# pwr.net
KiCad netlist of a schematic drawn in EAGLE
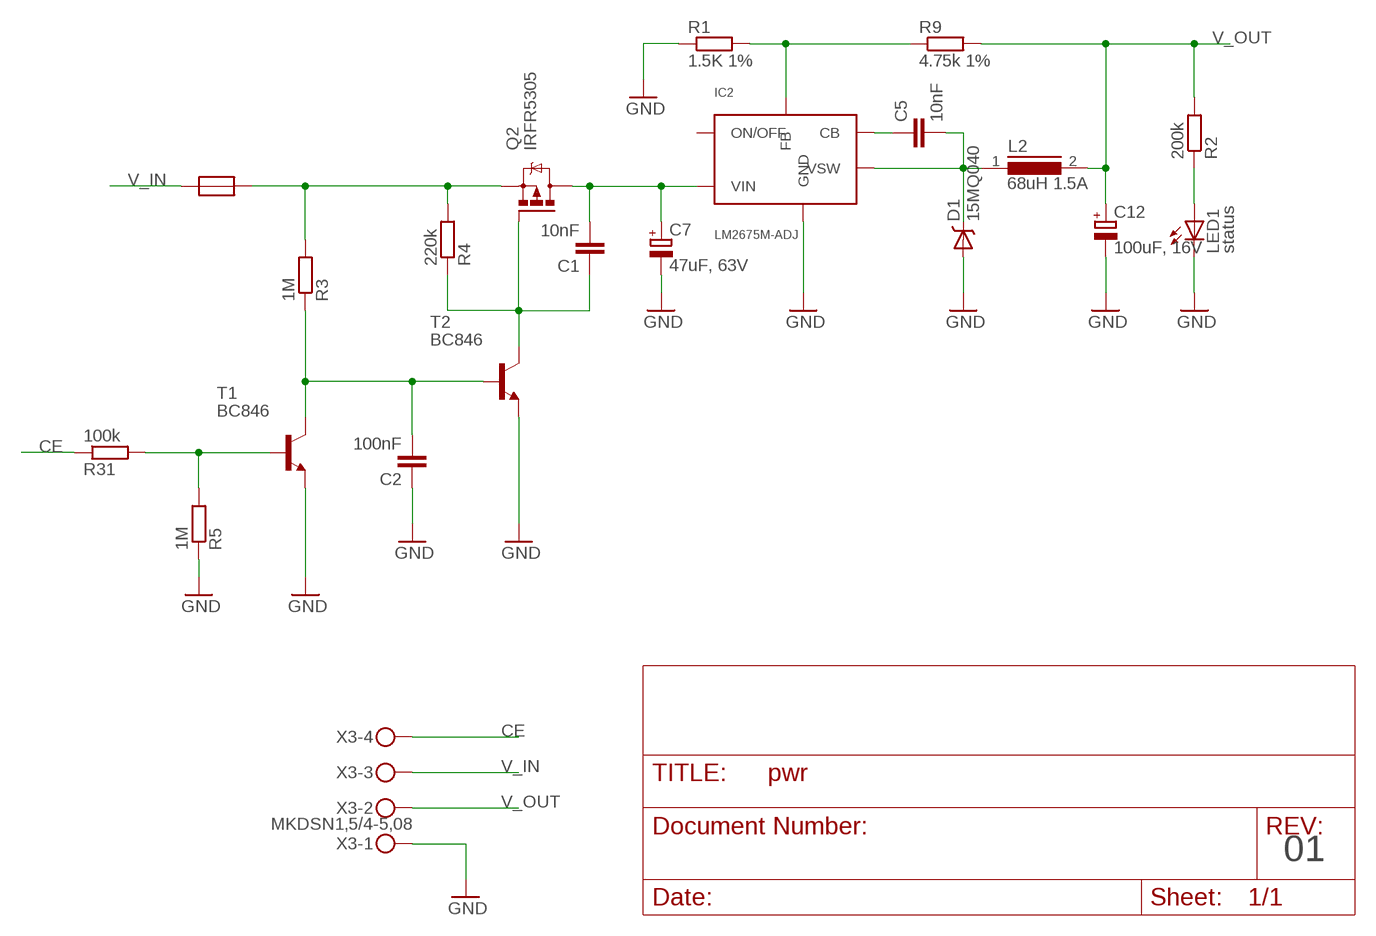
[diagram p0: schematic, sheet 1]

(export (version "E")
  (design (tool "Eeschema 10.0.6"))
  (components
    (comp (ref "C1")
      (value "10nF")
      (footprint "eagle-import:C0805")
      (libsource (lib "eagle-import") (part "C-EUC0805"))
    )
    (comp (ref "C2")
      (value "100nF")
      (footprint "eagle-import:C0805")
      (libsource (lib "eagle-import") (part "C-EUC0805"))
    )
    (comp (ref "C5")
      (value "10nF")
      (footprint "eagle-import:C0805")
      (libsource (lib "eagle-import") (part "C-EUC0805"))
    )
    (comp (ref "C7")
      (value "47uF, 63V")
      (footprint "eagle-import:PANASONIC_F")
      (libsource (lib "eagle-import") (part "CPOL-EUF"))
    )
    (comp (ref "C12")
      (value "100uF, 16V")
      (footprint "eagle-import:PANASONIC_D")
      (libsource (lib "eagle-import") (part "CPOL-EUD"))
    )
    (comp (ref "D1")
      (value "15MQ040")
      (footprint "eagle-import:SMA-DIODE")
      (libsource (lib "eagle-import") (part "DIODE-SCHOTTKY-MBRA140"))
    )
    (comp (ref "IC2")
      (value "LM2675M-ADJ")
      (footprint "eagle-import:SO-08")
      (libsource (lib "eagle-import") (part "LM2674"))
    )
    (comp (ref "L2")
      (value "68uH 1.5A")
      (footprint "eagle-import:DR125")
      (libsource (lib "eagle-import") (part "DR125"))
    )
    (comp (ref "LED1")
      (value "status")
      (footprint "eagle-import:CHIP-LED0805")
      (libsource (lib "eagle-import") (part "LEDCHIP-LED0805"))
    )
    (comp (ref "Q2")
      (value "IRFR5305")
      (footprint "eagle-import:D-PAK_TO252AA")
      (libsource (lib "eagle-import") (part "IRF?5305R"))
    )
    (comp (ref "R1")
      (value "1.5K 1%")
      (footprint "eagle-import:R0805W")
      (libsource (lib "eagle-import") (part "R-EU_R0805W"))
    )
    (comp (ref "R2")
      (value "200k")
      (footprint "eagle-import:R0805W")
      (libsource (lib "eagle-import") (part "R-EU_R0805W"))
    )
    (comp (ref "R3")
      (value "1M")
      (footprint "eagle-import:R0805W")
      (libsource (lib "eagle-import") (part "R-EU_R0805W"))
    )
    (comp (ref "R4")
      (value "220k")
      (footprint "eagle-import:R0805W")
      (libsource (lib "eagle-import") (part "R-EU_R0805W"))
    )
    (comp (ref "R5")
      (value "1M")
      (footprint "eagle-import:R0805W")
      (libsource (lib "eagle-import") (part "R-EU_R0805W"))
    )
    (comp (ref "R9")
      (value "4.75k 1%")
      (footprint "eagle-import:R0805W")
      (libsource (lib "eagle-import") (part "R-EU_R0805W"))
    )
    (comp (ref "R31")
      (value "100k")
      (footprint "eagle-import:R0805W")
      (libsource (lib "eagle-import") (part "R-EU_R0805W"))
    )
    (comp (ref "T1")
      (value "BC846")
      (footprint "eagle-import:SOT23")
      (libsource (lib "eagle-import") (part "BC846"))
    )
    (comp (ref "T2")
      (value "BC846")
      (footprint "eagle-import:SOT23")
      (libsource (lib "eagle-import") (part "BC846"))
    )
    (comp (ref "U$1")
      (value "RESETTABLE_0805")
      (footprint "eagle-import:0805W")
      (libsource (lib "eagle-import") (part "RESETTABLE_0805"))
    )
    (comp (ref "X3")
      (value "MKDSN1,5/4-5,08")
      (footprint "eagle-import:MKDSN1,5_4-5,08")
      (fields (field (name "MPN") "SMKDSN1,5/4-5,08"))
      (libsource (lib "eagle-import") (part "MKDSN1,5/4-5,08"))
    )
  )
  (nets
    (net (code "1") (name "/CE") (class "Default")
      (node (ref "R31") (pin "1") (pinfunction "1_1") (pintype "passive"))
      (node (ref "X3") (pin "4") (pinfunction "KL_4") (pintype "passive"))
    )
    (net (code "2") (name "/V_IN") (class "Default")
      (node (ref "U$1") (pin "1") (pinfunction "P$1_1") (pintype "bidirectional"))
      (node (ref "X3") (pin "3") (pinfunction "KL_3") (pintype "passive"))
    )
    (net (code "3") (name "/V_OUT") (class "Default")
      (node (ref "C12") (pin "+") (pinfunction "+_+") (pintype "passive"))
      (node (ref "L2") (pin "2") (pinfunction "2_2") (pintype "passive"))
      (node (ref "R2") (pin "2") (pinfunction "2_2") (pintype "passive"))
      (node (ref "R9") (pin "2") (pinfunction "2_2") (pintype "passive"))
      (node (ref "X3") (pin "2") (pinfunction "KL_2") (pintype "passive"))
    )
    (net (code "4") (name "GND") (class "Default")
      (node (ref "C12") (pin "-") (pinfunction "-_-") (pintype "passive"))
      (node (ref "C2") (pin "1") (pinfunction "1_1") (pintype "passive"))
      (node (ref "C7") (pin "-") (pinfunction "-_-") (pintype "passive"))
      (node (ref "D1") (pin "A") (pinfunction "A_A") (pintype "passive"))
      (node (ref "IC2") (pin "6") (pinfunction "GND_6") (pintype "bidirectional"))
      (node (ref "LED1") (pin "C") (pinfunction "C_C") (pintype "passive"))
      (node (ref "R1") (pin "1") (pinfunction "1_1") (pintype "passive"))
      (node (ref "R5") (pin "1") (pinfunction "1_1") (pintype "passive"))
      (node (ref "T1") (pin "2") (pinfunction "E_2") (pintype "passive"))
      (node (ref "T2") (pin "2") (pinfunction "E_2") (pintype "passive"))
      (node (ref "X3") (pin "1") (pinfunction "KL_1") (pintype "passive"))
    )
    (net (code "5") (name "Net-(IC2-CB)") (class "Default")
      (node (ref "C5") (pin "1") (pinfunction "1_1") (pintype "passive"))
      (node (ref "IC2") (pin "1") (pinfunction "CB_1") (pintype "bidirectional"))
    )
    (net (code "6") (name "Net-(IC2-FB)") (class "Default")
      (node (ref "IC2") (pin "4") (pinfunction "FB_4") (pintype "bidirectional"))
      (node (ref "R1") (pin "2") (pinfunction "2_2") (pintype "passive"))
      (node (ref "R9") (pin "1") (pinfunction "1_1") (pintype "passive"))
    )
    (net (code "7") (name "Net-(IC2-VIN)") (class "Default")
      (node (ref "C1") (pin "2") (pinfunction "2_2") (pintype "passive"))
      (node (ref "C7") (pin "+") (pinfunction "+_+") (pintype "passive"))
      (node (ref "IC2") (pin "7") (pinfunction "VIN_7") (pintype "bidirectional"))
      (node (ref "Q2") (pin "4") (pinfunction "D_4") (pintype "passive"))
    )
    (net (code "8") (name "Net-(IC2-VSW)") (class "Default")
      (node (ref "C5") (pin "2") (pinfunction "2_2") (pintype "passive"))
      (node (ref "D1") (pin "C") (pinfunction "C_C") (pintype "passive"))
      (node (ref "IC2") (pin "8") (pinfunction "VSW_8") (pintype "bidirectional"))
      (node (ref "L2") (pin "1") (pinfunction "1_1") (pintype "passive"))
    )
    (net (code "9") (name "Net-(LED1-PadA)") (class "Default")
      (node (ref "LED1") (pin "A") (pinfunction "A_A") (pintype "passive"))
      (node (ref "R2") (pin "1") (pinfunction "1_1") (pintype "passive"))
    )
    (net (code "10") (name "Net-(Q2-G)") (class "Default")
      (node (ref "C1") (pin "1") (pinfunction "1_1") (pintype "passive"))
      (node (ref "Q2") (pin "1") (pinfunction "G_1") (pintype "passive"))
      (node (ref "R4") (pin "1") (pinfunction "1_1") (pintype "passive"))
      (node (ref "T2") (pin "3") (pinfunction "C_3") (pintype "passive"))
    )
    (net (code "11") (name "Net-(Q2-S)") (class "Default")
      (node (ref "Q2") (pin "3") (pinfunction "S_3") (pintype "passive"))
      (node (ref "R3") (pin "2") (pinfunction "2_2") (pintype "passive"))
      (node (ref "R4") (pin "2") (pinfunction "2_2") (pintype "passive"))
      (node (ref "U$1") (pin "2") (pinfunction "P$2_2") (pintype "bidirectional"))
    )
    (net (code "12") (name "Net-(T1-B)") (class "Default")
      (node (ref "R31") (pin "2") (pinfunction "2_2") (pintype "passive"))
      (node (ref "R5") (pin "2") (pinfunction "2_2") (pintype "passive"))
      (node (ref "T1") (pin "1") (pinfunction "B_1") (pintype "passive"))
    )
    (net (code "13") (name "Net-(T1-C)") (class "Default")
      (node (ref "C2") (pin "2") (pinfunction "2_2") (pintype "passive"))
      (node (ref "R3") (pin "1") (pinfunction "1_1") (pintype "passive"))
      (node (ref "T1") (pin "3") (pinfunction "C_3") (pintype "passive"))
      (node (ref "T2") (pin "1") (pinfunction "B_1") (pintype "passive"))
    )
    (net (code "14") (name "unconnected-(IC2-ON{slash}OFF-Pad5)") (class "Default")
      (node (ref "IC2") (pin "5") (pinfunction "ON/OFF_5") (pintype "bidirectional"))
    )
  )
)
